# Power.net
KiCad netlist of a schematic drawn in Altium Designer
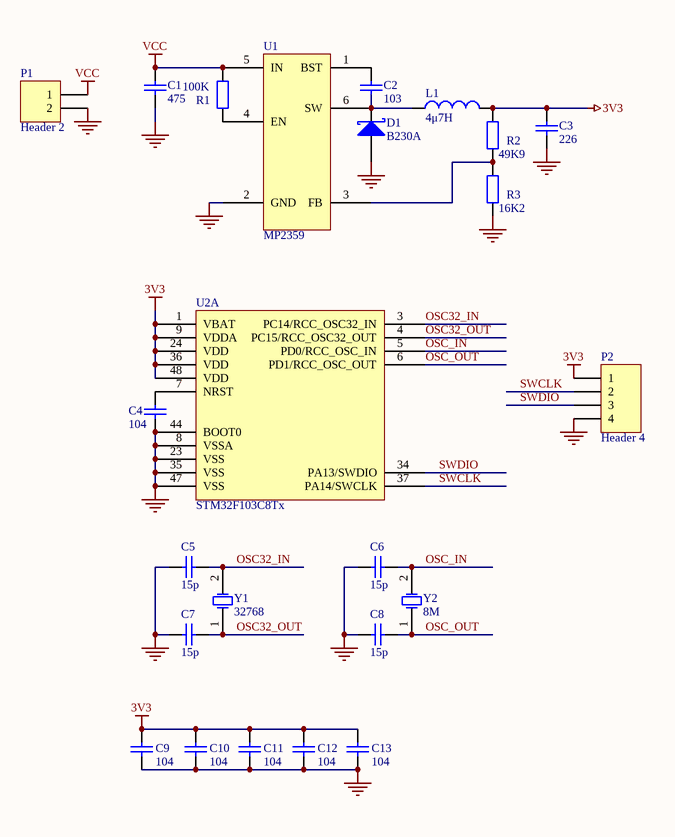
[diagram p0: Power.SchDoc]

(export (version "E")
  (design (tool "Eeschema 10.0.6"))
  (components
    (comp (ref "C1")
      (value "475")
      (footprint "MicroControl:C1206")
      (description "Capacitor")
      (fields (field (name "PUBLISHER") "Altium Limited"))
      (libsource (lib "Miscellaneous Devices") (part "Cap"))
    )
    (comp (ref "C2")
      (value "103")
      (footprint "MicroControl:C0603")
      (description "Capacitor")
      (fields (field (name "PUBLISHER") "Altium Limited"))
      (libsource (lib "Miscellaneous Devices") (part "Cap"))
    )
    (comp (ref "C3")
      (value "226")
      (footprint "MicroControl:C0805")
      (description "Capacitor")
      (fields (field (name "PUBLISHER") "Altium Limited"))
      (libsource (lib "Miscellaneous Devices") (part "Cap"))
    )
    (comp (ref "C4")
      (value "104")
      (footprint "MicroControl:C0603")
      (description "Capacitor")
      (fields (field (name "PUBLISHER") "Altium Limited"))
      (libsource (lib "Miscellaneous Devices") (part "Cap"))
    )
    (comp (ref "C5")
      (value "15p")
      (footprint "MicroControl:C0603")
      (description "Capacitor")
      (fields (field (name "PUBLISHER") "Altium Limited"))
      (libsource (lib "Miscellaneous Devices") (part "Cap"))
    )
    (comp (ref "C6")
      (value "15p")
      (footprint "MicroControl:C0603")
      (description "Capacitor")
      (fields (field (name "PUBLISHER") "Altium Limited"))
      (libsource (lib "Miscellaneous Devices") (part "Cap"))
    )
    (comp (ref "C7")
      (value "15p")
      (footprint "MicroControl:C0603")
      (description "Capacitor")
      (fields (field (name "PUBLISHER") "Altium Limited"))
      (libsource (lib "Miscellaneous Devices") (part "Cap"))
    )
    (comp (ref "C8")
      (value "15p")
      (footprint "MicroControl:C0603")
      (description "Capacitor")
      (fields (field (name "PUBLISHER") "Altium Limited"))
      (libsource (lib "Miscellaneous Devices") (part "Cap"))
    )
    (comp (ref "C9")
      (value "104")
      (footprint "MicroControl:C0603")
      (description "Capacitor")
      (fields (field (name "PUBLISHER") "Altium Limited"))
      (libsource (lib "Miscellaneous Devices") (part "Cap"))
    )
    (comp (ref "C10")
      (value "104")
      (footprint "MicroControl:C0603")
      (description "Capacitor")
      (fields (field (name "PUBLISHER") "Altium Limited"))
      (libsource (lib "Miscellaneous Devices") (part "Cap"))
    )
    (comp (ref "C11")
      (value "104")
      (footprint "MicroControl:C0603")
      (description "Capacitor")
      (fields (field (name "PUBLISHER") "Altium Limited"))
      (libsource (lib "Miscellaneous Devices") (part "Cap"))
    )
    (comp (ref "C12")
      (value "104")
      (footprint "MicroControl:C0603")
      (description "Capacitor")
      (fields (field (name "PUBLISHER") "Altium Limited"))
      (libsource (lib "Miscellaneous Devices") (part "Cap"))
    )
    (comp (ref "C13")
      (value "104")
      (footprint "MicroControl:C0603")
      (description "Capacitor")
      (fields (field (name "PUBLISHER") "Altium Limited"))
      (libsource (lib "Miscellaneous Devices") (part "Cap"))
    )
    (comp (ref "D1")
      (value "B230A")
      (footprint "MicroControl:SMA")
      (description "Silicon AF Schottky Diode for High-Speed Switching")
      (fields (field (name "PUBLISHER") "Altium Limited"))
      (libsource (lib "Miscellaneous Devices") (part "Diode BAS70"))
    )
    (comp (ref "L1")
      (value "4μ7H")
      (footprint "MicroControl:L4X4")
      (fields (field (name "PUBLISHER") "Altium Limited"))
      (libsource (lib "Miscellaneous Devices") (part "Inductor"))
    )
    (comp (ref "P1")
      (value "Header 2")
      (footprint "Connetor:XH2P54P2")
      (description "Header, 2-Pin, Right Angle")
      (fields (field (name "PUBLISHER") "Altium Limited"))
      (libsource (lib "Miscellaneous Connectors") (part "Header 2H"))
    )
    (comp (ref "P2")
      (value "Header 4")
      (footprint "Connetor:SIP4")
      (description "Header, 4-Pin")
      (fields (field (name "PUBLISHER") "Altium Limited"))
      (libsource (lib "Miscellaneous Connectors") (part "Header 4"))
    )
    (comp (ref "R1")
      (value "100K")
      (footprint "MicroControl:R0603")
      (description "Resistor")
      (fields (field (name "PUBLISHER") "Altium Limited"))
      (libsource (lib "Miscellaneous Devices") (part "Res2"))
    )
    (comp (ref "R2")
      (value "49K9")
      (footprint "MicroControl:R0603")
      (description "Resistor")
      (fields (field (name "PUBLISHER") "Altium Limited"))
      (libsource (lib "Miscellaneous Devices") (part "Res2"))
    )
    (comp (ref "R3")
      (value "16K2")
      (footprint "MicroControl:R0603")
      (description "Resistor")
      (fields (field (name "PUBLISHER") "Altium Limited"))
      (libsource (lib "Miscellaneous Devices") (part "Res2"))
    )
    (comp (ref "U1") (value "MP2359") (footprint "SOT23-6") (libsource (lib "yinhaonanLib") (part "MP2359")))
    (comp (ref "U2")
      (value "STM32F103C8Tx")
      (footprint "Integrated_Circuit:PQFP48")
      (libsource (lib "yinhaonanLib") (part "STM32F103C8Tx"))
    )
    (comp (ref "Y1")
      (value "32768")
      (footprint "MicroControl:FC-135")
      (description "Crystal Oscillator")
      (fields (field (name "PUBLISHER") "Altium Limited"))
      (libsource (lib "Miscellaneous Devices") (part "XTAL"))
    )
    (comp (ref "Y2")
      (value "8M")
      (footprint "MicroControl:CY5032")
      (description "Crystal Oscillator")
      (fields (field (name "PUBLISHER") "Altium Limited"))
      (libsource (lib "Miscellaneous Devices") (part "XTAL"))
    )
  )
  (nets
    (net (code "1") (name "/OSC32_IN") (class "Default")
      (node (ref "C5") (pin "1") (pinfunction "1_1") (pintype "passive"))
      (node (ref "U2") (pin "3") (pinfunction "PC14/RCC_OSC32_IN_3") (pintype "passive"))
      (node (ref "Y1") (pin "2") (pinfunction "OSC2_2") (pintype "passive"))
    )
    (net (code "2") (name "/OSC32_OUT") (class "Default")
      (node (ref "C7") (pin "1") (pinfunction "1_1") (pintype "passive"))
      (node (ref "U2") (pin "4") (pinfunction "PC15/RCC_OSC32_OUT_4") (pintype "passive"))
      (node (ref "Y1") (pin "1") (pinfunction "OSC1_1") (pintype "passive"))
    )
    (net (code "3") (name "/OSC_IN") (class "Default")
      (node (ref "C6") (pin "1") (pinfunction "1_1") (pintype "passive"))
      (node (ref "U2") (pin "5") (pinfunction "PD0/RCC_OSC_IN_5") (pintype "passive"))
      (node (ref "Y2") (pin "2") (pinfunction "OSC2_2") (pintype "passive"))
    )
    (net (code "4") (name "/OSC_OUT") (class "Default")
      (node (ref "C8") (pin "1") (pinfunction "1_1") (pintype "passive"))
      (node (ref "U2") (pin "6") (pinfunction "PD1/RCC_OSC_OUT_6") (pintype "passive"))
      (node (ref "Y2") (pin "1") (pinfunction "OSC1_1") (pintype "passive"))
    )
    (net (code "5") (name "/SWCLK") (class "Default")
      (node (ref "P2") (pin "2") (pinfunction "2_2") (pintype "passive"))
      (node (ref "U2") (pin "37") (pinfunction "PA14/SWCLK_37") (pintype "passive"))
    )
    (net (code "6") (name "/SWDIO") (class "Default")
      (node (ref "P2") (pin "3") (pinfunction "3_3") (pintype "passive"))
      (node (ref "U2") (pin "34") (pinfunction "PA13/SWDIO_34") (pintype "passive"))
    )
    (net (code "7") (name "3V3") (class "Default")
      (node (ref "C10") (pin "2") (pinfunction "2_2") (pintype "passive"))
      (node (ref "C11") (pin "2") (pinfunction "2_2") (pintype "passive"))
      (node (ref "C12") (pin "2") (pinfunction "2_2") (pintype "passive"))
      (node (ref "C13") (pin "2") (pinfunction "2_2") (pintype "passive"))
      (node (ref "C3") (pin "2") (pinfunction "2_2") (pintype "passive"))
      (node (ref "C9") (pin "2") (pinfunction "2_2") (pintype "passive"))
      (node (ref "L1") (pin "2") (pinfunction "2_2") (pintype "passive"))
      (node (ref "P2") (pin "1") (pinfunction "1_1") (pintype "passive"))
      (node (ref "R2") (pin "1") (pinfunction "1_1") (pintype "passive"))
      (node (ref "U2") (pin "1") (pinfunction "VBAT_1") (pintype "passive"))
      (node (ref "U2") (pin "24") (pinfunction "VDD_24") (pintype "passive"))
      (node (ref "U2") (pin "36") (pinfunction "VDD_36") (pintype "passive"))
      (node (ref "U2") (pin "48") (pinfunction "VDD_48") (pintype "passive"))
      (node (ref "U2") (pin "9") (pinfunction "VDDA_9") (pintype "passive"))
    )
    (net (code "8") (name "GND") (class "Default")
      (node (ref "C1") (pin "1") (pinfunction "1_1") (pintype "passive"))
      (node (ref "C10") (pin "1") (pinfunction "1_1") (pintype "passive"))
      (node (ref "C11") (pin "1") (pinfunction "1_1") (pintype "passive"))
      (node (ref "C12") (pin "1") (pinfunction "1_1") (pintype "passive"))
      (node (ref "C13") (pin "1") (pinfunction "1_1") (pintype "passive"))
      (node (ref "C3") (pin "1") (pinfunction "1_1") (pintype "passive"))
      (node (ref "C4") (pin "1") (pinfunction "1_1") (pintype "passive"))
      (node (ref "C5") (pin "2") (pinfunction "2_2") (pintype "passive"))
      (node (ref "C6") (pin "2") (pinfunction "2_2") (pintype "passive"))
      (node (ref "C7") (pin "2") (pinfunction "2_2") (pintype "passive"))
      (node (ref "C8") (pin "2") (pinfunction "2_2") (pintype "passive"))
      (node (ref "C9") (pin "1") (pinfunction "1_1") (pintype "passive"))
      (node (ref "D1") (pin "1") (pinfunction "A_1") (pintype "passive"))
      (node (ref "P1") (pin "2") (pinfunction "2_2") (pintype "passive"))
      (node (ref "P2") (pin "4") (pinfunction "4_4") (pintype "passive"))
      (node (ref "R3") (pin "2") (pinfunction "2_2") (pintype "passive"))
      (node (ref "U1") (pin "2") (pinfunction "GND_2") (pintype "passive"))
      (node (ref "U2") (pin "23") (pinfunction "VSS_23") (pintype "passive"))
      (node (ref "U2") (pin "35") (pinfunction "VSS_35") (pintype "passive"))
      (node (ref "U2") (pin "44") (pinfunction "BOOT0_44") (pintype "passive"))
      (node (ref "U2") (pin "47") (pinfunction "VSS_47") (pintype "passive"))
      (node (ref "U2") (pin "8") (pinfunction "VSSA_8") (pintype "passive"))
    )
    (net (code "9") (name "Net-(D1-K)") (class "Default")
      (node (ref "C2") (pin "1") (pinfunction "1_1") (pintype "passive"))
      (node (ref "D1") (pin "2") (pinfunction "K_2") (pintype "passive"))
      (node (ref "L1") (pin "1") (pinfunction "1_1") (pintype "passive"))
      (node (ref "U1") (pin "6") (pinfunction "SW_6") (pintype "passive"))
    )
    (net (code "10") (name "Net-(U1-BST)") (class "Default")
      (node (ref "C2") (pin "2") (pinfunction "2_2") (pintype "passive"))
      (node (ref "U1") (pin "1") (pinfunction "BST_1") (pintype "passive"))
    )
    (net (code "11") (name "Net-(U1-EN)") (class "Default")
      (node (ref "R1") (pin "2") (pinfunction "2_2") (pintype "passive"))
      (node (ref "U1") (pin "4") (pinfunction "EN_4") (pintype "passive"))
    )
    (net (code "12") (name "Net-(U1-FB)") (class "Default")
      (node (ref "R2") (pin "2") (pinfunction "2_2") (pintype "passive"))
      (node (ref "R3") (pin "1") (pinfunction "1_1") (pintype "passive"))
      (node (ref "U1") (pin "3") (pinfunction "FB_3") (pintype "passive"))
    )
    (net (code "13") (name "Net-(U2A-NRST)") (class "Default")
      (node (ref "C4") (pin "2") (pinfunction "2_2") (pintype "passive"))
      (node (ref "U2") (pin "7") (pinfunction "NRST_7") (pintype "passive"))
    )
    (net (code "14") (name "VCC") (class "Default")
      (node (ref "C1") (pin "2") (pinfunction "2_2") (pintype "passive"))
      (node (ref "P1") (pin "1") (pinfunction "1_1") (pintype "passive"))
      (node (ref "R1") (pin "1") (pinfunction "1_1") (pintype "passive"))
      (node (ref "U1") (pin "5") (pinfunction "IN_5") (pintype "passive"))
    )
  )
)
